# optocsatolo.net
KiCad netlist of a schematic drawn in EAGLE
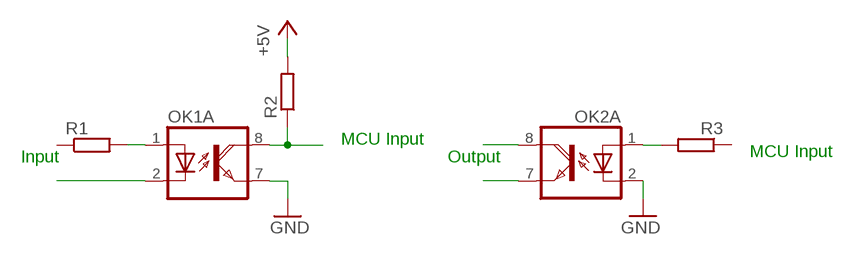
[diagram p0: schematic, sheet 1]

(export (version "E")
  (design (tool "Eeschema 10.0.6"))
  (components
    (comp (ref "OK1")
      (value "TIL198")
      (footprint "eagle-import:DIL08")
      (libsource (lib "eagle-import") (part "TIL198"))
    )
    (comp (ref "OK2")
      (value "TIL198")
      (footprint "eagle-import:DIL08")
      (libsource (lib "eagle-import") (part "TIL198"))
    )
    (comp (ref "R1")
      (value "R-EU_R1206W")
      (footprint "eagle-import:R1206W")
      (libsource (lib "eagle-import") (part "R-EU_R1206W"))
    )
    (comp (ref "R2")
      (value "R-EU_R1206W")
      (footprint "eagle-import:R1206W")
      (libsource (lib "eagle-import") (part "R-EU_R1206W"))
    )
    (comp (ref "R3")
      (value "R-EU_R1206W")
      (footprint "eagle-import:R1206W")
      (libsource (lib "eagle-import") (part "R-EU_R1206W"))
    )
  )
  (nets
    (net (code "1") (name "+5V") (class "Default")
      (node (ref "R2") (pin "2") (pinfunction "2_2") (pintype "passive"))
    )
    (net (code "2") (name "GND") (class "Default")
      (node (ref "OK1") (pin "7") (pinfunction "EMI_7") (pintype "passive"))
      (node (ref "OK2") (pin "2") (pinfunction "C_2") (pintype "passive"))
    )
    (net (code "3") (name "Net-(OK1A-A)") (class "Default")
      (node (ref "OK1") (pin "1") (pinfunction "A_1") (pintype "passive"))
      (node (ref "R1") (pin "2") (pinfunction "2_2") (pintype "passive"))
    )
    (net (code "4") (name "Net-(OK1A-COL)") (class "Default")
      (node (ref "OK1") (pin "8") (pinfunction "COL_8") (pintype "passive"))
      (node (ref "R2") (pin "1") (pinfunction "1_1") (pintype "passive"))
    )
    (net (code "5") (name "Net-(OK2A-A)") (class "Default")
      (node (ref "OK2") (pin "1") (pinfunction "A_1") (pintype "passive"))
      (node (ref "R3") (pin "2") (pinfunction "2_2") (pintype "passive"))
    )
    (net (code "6") (name "unconnected-(OK1A-C-Pad2)") (class "Default")
      (node (ref "OK1") (pin "2") (pinfunction "C_2") (pintype "passive"))
    )
    (net (code "7") (name "unconnected-(OK2A-COL-Pad8)") (class "Default")
      (node (ref "OK2") (pin "8") (pinfunction "COL_8") (pintype "passive"))
    )
    (net (code "8") (name "unconnected-(OK2A-EMI-Pad7)") (class "Default")
      (node (ref "OK2") (pin "7") (pinfunction "EMI_7") (pintype "passive"))
    )
    (net (code "9") (name "unconnected-(R1-Pad1)") (class "Default")
      (node (ref "R1") (pin "1") (pinfunction "1_1") (pintype "passive"))
    )
    (net (code "10") (name "unconnected-(R3-Pad1)") (class "Default")
      (node (ref "R3") (pin "1") (pinfunction "1_1") (pintype "passive"))
    )
  )
)
